# USB_Hub_AMCbox.net
KiCad netlist of a schematic drawn in Altium Designer
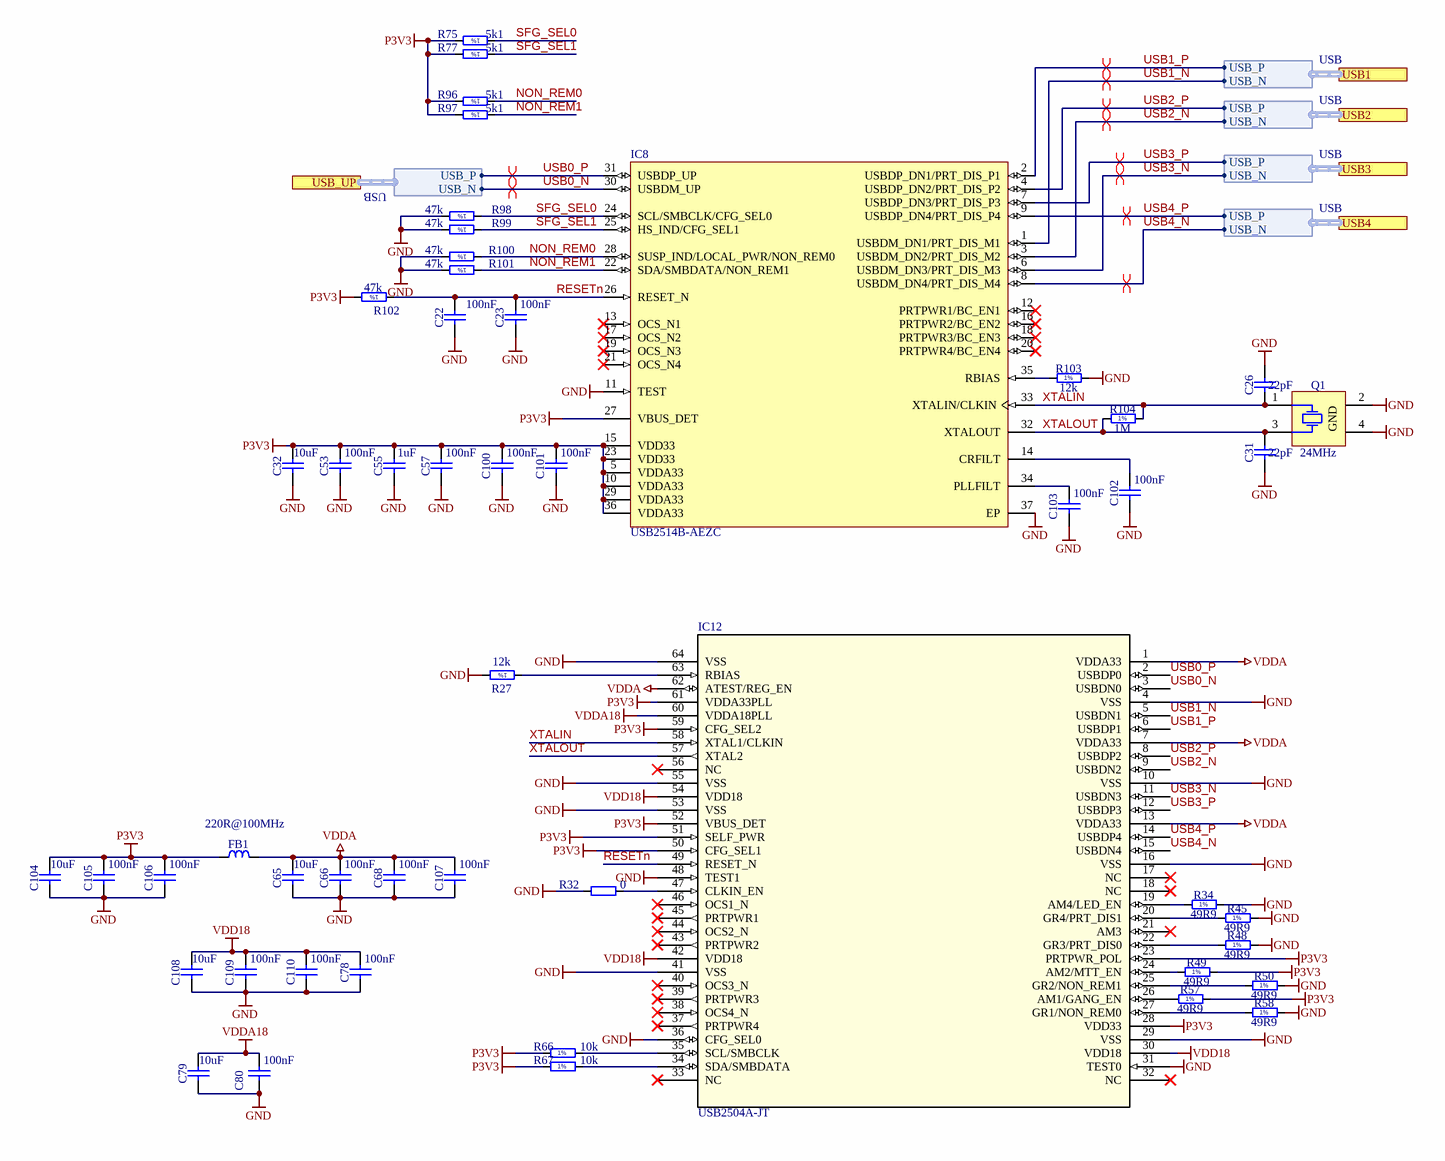
[diagram p0: USB_Hub_AMCbox.SchDoc]

(export (version "E")
  (design (tool "Eeschema 10.0.6"))
  (components
    (comp (ref "C22")
      (value "100nF")
      (footprint "CAPC0603X33N")
      (description "Non-polarised capacitor")
      (fields
        (field (name "PART NUMBER") "CC0201_100NF_6.3V_10%_X5R")
        (field (name "VOLTAGE") "6.3V")
        (field (name "AUTHOR") "CERN DEM JLC")
      )
      (libsource (lib "Capacitors") (part "Capacitor - non polarized"))
    )
    (comp (ref "C23")
      (value "100nF")
      (footprint "CAPC0603X33N")
      (description "Non-polarised capacitor")
      (fields
        (field (name "PART NUMBER") "CC0201_100NF_6.3V_10%_X5R")
        (field (name "VOLTAGE") "6.3V")
        (field (name "AUTHOR") "CERN DEM JLC")
      )
      (libsource (lib "Capacitors") (part "Capacitor - non polarized"))
    )
    (comp (ref "C26")
      (value "22pF")
      (footprint "CAPC1005X55N")
      (description "Non-polarised capacitor")
      (fields
        (field (name "PART NUMBER") "CC0402_22PF_50V_5%_C0G")
        (field (name "VOLTAGE") "50V")
        (field (name "AUTHOR") "CERN DEM JLC")
      )
      (libsource (lib "Capacitors") (part "Capacitor - non polarized"))
    )
    (comp (ref "C31")
      (value "22pF")
      (footprint "CAPC1005X55N")
      (description "Non-polarised capacitor")
      (fields
        (field (name "PART NUMBER") "CC0402_22PF_50V_5%_C0G")
        (field (name "VOLTAGE") "50V")
        (field (name "AUTHOR") "CERN DEM JLC")
      )
      (libsource (lib "Capacitors") (part "Capacitor - non polarized"))
    )
    (comp (ref "C32")
      (value "10uF")
      (footprint "CAPC1608X80N")
      (description "Non-polarised capacitor")
      (fields
        (field (name "PART NUMBER") "CC0603_10UF_16V_20%_X5R")
        (field (name "VOLTAGE") "16V")
        (field (name "AUTHOR") "CERN DEM MR")
      )
      (libsource (lib "Capacitors") (part "Capacitor - non polarized"))
    )
    (comp (ref "C53")
      (value "100nF")
      (footprint "CAPC0603X33N")
      (description "Non-polarised capacitor")
      (fields
        (field (name "PART NUMBER") "CC0201_100NF_6.3V_10%_X5R")
        (field (name "VOLTAGE") "6.3V")
        (field (name "AUTHOR") "CERN DEM JLC")
      )
      (libsource (lib "Capacitors") (part "Capacitor - non polarized"))
    )
    (comp (ref "C55")
      (value "1uF")
      (footprint "CAPC1005X55N")
      (description "Non-polarised capacitor")
      (fields
        (field (name "PART NUMBER") "CC0402_1UF_16V_10%_X5R")
        (field (name "VOLTAGE") "16V")
        (field (name "AUTHOR") "CERN DEM JLC")
      )
      (libsource (lib "Capacitors") (part "Capacitor - non polarized"))
    )
    (comp (ref "C57")
      (value "100nF")
      (footprint "CAPC0603X33N")
      (description "Non-polarised capacitor")
      (fields
        (field (name "PART NUMBER") "CC0201_100NF_6.3V_10%_X5R")
        (field (name "VOLTAGE") "6.3V")
        (field (name "AUTHOR") "CERN DEM JLC")
      )
      (libsource (lib "Capacitors") (part "Capacitor - non polarized"))
    )
    (comp (ref "C65")
      (value "10uF")
      (footprint "CAPC1608X80N")
      (description "Non-polarised capacitor")
      (fields
        (field (name "PART NUMBER") "CC0603_10UF_16V_20%_X5R")
        (field (name "VOLTAGE") "16V")
        (field (name "AUTHOR") "CERN DEM MR")
      )
      (libsource (lib "Capacitors") (part "Capacitor - non polarized"))
    )
    (comp (ref "C66")
      (value "100nF")
      (footprint "CAPC0603X33N")
      (description "Non-polarised capacitor")
      (fields
        (field (name "PART NUMBER") "CC0201_100NF_6.3V_10%_X5R")
        (field (name "VOLTAGE") "6.3V")
        (field (name "AUTHOR") "CERN DEM JLC")
      )
      (libsource (lib "Capacitors") (part "Capacitor - non polarized"))
    )
    (comp (ref "C68")
      (value "100nF")
      (footprint "CAPC0603X33N")
      (description "Non-polarised capacitor")
      (fields
        (field (name "PART NUMBER") "CC0201_100NF_6.3V_10%_X5R")
        (field (name "VOLTAGE") "6.3V")
        (field (name "AUTHOR") "CERN DEM JLC")
      )
      (libsource (lib "Capacitors") (part "Capacitor - non polarized"))
    )
    (comp (ref "C78")
      (value "100nF")
      (footprint "CAPC0603X33N")
      (description "Non-polarised capacitor")
      (fields
        (field (name "PART NUMBER") "CC0201_100NF_6.3V_10%_X5R")
        (field (name "VOLTAGE") "6.3V")
        (field (name "AUTHOR") "CERN DEM JLC")
      )
      (libsource (lib "Capacitors") (part "Capacitor - non polarized"))
    )
    (comp (ref "C79")
      (value "10uF")
      (footprint "CAPC1608X80N")
      (description "Non-polarised capacitor")
      (fields
        (field (name "PART NUMBER") "CC0603_10UF_16V_20%_X5R")
        (field (name "VOLTAGE") "16V")
        (field (name "AUTHOR") "CERN DEM MR")
      )
      (libsource (lib "Capacitors") (part "Capacitor - non polarized"))
    )
    (comp (ref "C80")
      (value "100nF")
      (footprint "CAPC0603X33N")
      (description "Non-polarised capacitor")
      (fields
        (field (name "PART NUMBER") "CC0201_100NF_6.3V_10%_X5R")
        (field (name "VOLTAGE") "6.3V")
        (field (name "AUTHOR") "CERN DEM JLC")
      )
      (libsource (lib "Capacitors") (part "Capacitor - non polarized"))
    )
    (comp (ref "C100")
      (value "100nF")
      (footprint "CAPC0603X33N")
      (description "Non-polarised capacitor")
      (fields
        (field (name "PART NUMBER") "CC0201_100NF_6.3V_10%_X5R")
        (field (name "VOLTAGE") "6.3V")
        (field (name "AUTHOR") "CERN DEM JLC")
      )
      (libsource (lib "Capacitors") (part "Capacitor - non polarized"))
    )
    (comp (ref "C101")
      (value "100nF")
      (footprint "CAPC0603X33N")
      (description "Non-polarised capacitor")
      (fields
        (field (name "PART NUMBER") "CC0201_100NF_6.3V_10%_X5R")
        (field (name "VOLTAGE") "6.3V")
        (field (name "AUTHOR") "CERN DEM JLC")
      )
      (libsource (lib "Capacitors") (part "Capacitor - non polarized"))
    )
    (comp (ref "C102")
      (value "100nF")
      (footprint "CAPC0603X33N")
      (description "Non-polarised capacitor")
      (fields
        (field (name "PART NUMBER") "CC0201_100NF_6.3V_10%_X5R")
        (field (name "VOLTAGE") "6.3V")
        (field (name "AUTHOR") "CERN DEM JLC")
      )
      (libsource (lib "Capacitors") (part "Capacitor - non polarized"))
    )
    (comp (ref "C103")
      (value "100nF")
      (footprint "CAPC0603X33N")
      (description "Non-polarised capacitor")
      (fields
        (field (name "PART NUMBER") "CC0201_100NF_6.3V_10%_X5R")
        (field (name "VOLTAGE") "6.3V")
        (field (name "AUTHOR") "CERN DEM JLC")
      )
      (libsource (lib "Capacitors") (part "Capacitor - non polarized"))
    )
    (comp (ref "C104")
      (value "10uF")
      (footprint "CAPC1608X80N")
      (description "Non-polarised capacitor")
      (fields
        (field (name "PART NUMBER") "CC0603_10UF_16V_20%_X5R")
        (field (name "VOLTAGE") "16V")
        (field (name "AUTHOR") "CERN DEM MR")
      )
      (libsource (lib "Capacitors") (part "Capacitor - non polarized"))
    )
    (comp (ref "C105")
      (value "100nF")
      (footprint "CAPC0603X33N")
      (description "Non-polarised capacitor")
      (fields
        (field (name "PART NUMBER") "CC0201_100NF_6.3V_10%_X5R")
        (field (name "VOLTAGE") "6.3V")
        (field (name "AUTHOR") "CERN DEM JLC")
      )
      (libsource (lib "Capacitors") (part "Capacitor - non polarized"))
    )
    (comp (ref "C106")
      (value "100nF")
      (footprint "CAPC0603X33N")
      (description "Non-polarised capacitor")
      (fields
        (field (name "PART NUMBER") "CC0201_100NF_6.3V_10%_X5R")
        (field (name "VOLTAGE") "6.3V")
        (field (name "AUTHOR") "CERN DEM JLC")
      )
      (libsource (lib "Capacitors") (part "Capacitor - non polarized"))
    )
    (comp (ref "C107")
      (value "100nF")
      (footprint "CAPC0603X33N")
      (description "Non-polarised capacitor")
      (fields
        (field (name "PART NUMBER") "CC0201_100NF_6.3V_10%_X5R")
        (field (name "VOLTAGE") "6.3V")
        (field (name "AUTHOR") "CERN DEM JLC")
      )
      (libsource (lib "Capacitors") (part "Capacitor - non polarized"))
    )
    (comp (ref "C108")
      (value "10uF")
      (footprint "CAPC1608X80N")
      (description "Non-polarised capacitor")
      (fields
        (field (name "PART NUMBER") "CC0603_10UF_16V_20%_X5R")
        (field (name "VOLTAGE") "16V")
        (field (name "AUTHOR") "CERN DEM MR")
      )
      (libsource (lib "Capacitors") (part "Capacitor - non polarized"))
    )
    (comp (ref "C109")
      (value "100nF")
      (footprint "CAPC0603X33N")
      (description "Non-polarised capacitor")
      (fields
        (field (name "PART NUMBER") "CC0201_100NF_6.3V_10%_X5R")
        (field (name "VOLTAGE") "6.3V")
        (field (name "AUTHOR") "CERN DEM JLC")
      )
      (libsource (lib "Capacitors") (part "Capacitor - non polarized"))
    )
    (comp (ref "C110")
      (value "100nF")
      (footprint "CAPC0603X33N")
      (description "Non-polarised capacitor")
      (fields
        (field (name "PART NUMBER") "CC0201_100NF_6.3V_10%_X5R")
        (field (name "VOLTAGE") "6.3V")
        (field (name "AUTHOR") "CERN DEM JLC")
      )
      (libsource (lib "Capacitors") (part "Capacitor - non polarized"))
    )
    (comp (ref "FB1")
      (value "220R@100MHz")
      (footprint "INDC2012X105N")
      (description "Inductor")
      (fields
        (field (name "PART NUMBER") "IND0805_MURATA_BLM21PG221SN1D")
        (field (name "POWER") "2A")
        (field (name "AUTHOR") "CERN DEM JLC")
      )
      (libsource (lib "Inductors & Transformers") (part "Inductor"))
    )
    (comp (ref "IC8")
      (value "USB2514B-AEZC")
      (footprint "MCHP-QFN-36_V")
      (description "USB 2.0 High-Speed Hub Controller, 4 Ports, 3 to 3.6 V, 0 to 85 degC, 36-Pin QFN, RoHS, Tray")
      (fields (field (name "MANUFACTURER") "Microchip"))
      (libsource (lib "Altium Content Vault") (part "MCHP-USB2514B-QFN-36"))
    )
    (comp (ref "IC12")
      (value "USB2504A-JT")
      (footprint "TQFP64_10x10MC_MCH")
      (description "Integrated USB 2.0 Compatible 4-Port Hub")
      (fields
        (field (name "MANUFACTURER") "Microchip")
        (field (name "COPYRIGHT") "Copyright (C) 2022 Ultra Librarian. All rights reserved.")
      )
      (libsource (lib "ICs_Analog_Interfaces") (part "IFC_USB2504A-JT"))
    )
    (comp (ref "Q1")
      (value "24MHz")
      (footprint "XTAL_PERICOM_FL")
      (description "Crystal 4 pins 1=XTAL Control 2=GND3=XTAL 4=GND")
      (fields
        (field (name "PART NUMBER") "XTAL_24MHZ_PERICOM_FL2400041")
        (field (name "MANUFACTURER") "PERICOM")
        (field (name "AUTHOR") "CERN DEM JLC")
      )
      (libsource (lib "ICs And Semiconductors") (part "Quartz Crystal 1X 2GND 3X 4GND"))
    )
    (comp (ref "R27")
      (value "12k")
      (footprint "RESC1005X40N")
      (description "Resistor - 1%")
      (fields
        (field (name "PART NUMBER") "R0402_12K_1%_0.0625W_100PPM")
        (field (name "POWER") "0.0625W")
        (field (name "AUTHOR") "CERN DEM JLC")
      )
      (libsource (lib "Resistors") (part "Resistor - 1%"))
    )
    (comp (ref "R32")
      (value "0")
      (footprint "RESC1005X40N")
      (description "Resistor")
      (fields
        (field (name "PART NUMBER") "R0402_0R_JUMPER")
        (field (name "MANUFACTURER") "GENERIC")
        (field (name "AUTHOR") "CERN DEM JLC")
      )
      (libsource (lib "Resistors") (part "Resistor"))
    )
    (comp (ref "R34")
      (value "49R9")
      (footprint "RESC1005X40N")
      (description "Resistor - 1%")
      (fields
        (field (name "PART NUMBER") "R0402_49R9_1%_0.0625W_100PPM")
        (field (name "POWER") "0.0625W")
        (field (name "AUTHOR") "CERN DEM JLC")
      )
      (libsource (lib "Resistors") (part "Resistor - 1%"))
    )
    (comp (ref "R45")
      (value "49R9")
      (footprint "RESC1005X40N")
      (description "Resistor - 1%")
      (fields
        (field (name "PART NUMBER") "R0402_49R9_1%_0.0625W_100PPM")
        (field (name "POWER") "0.0625W")
        (field (name "AUTHOR") "CERN DEM JLC")
      )
      (libsource (lib "Resistors") (part "Resistor - 1%"))
    )
    (comp (ref "R48")
      (value "49R9")
      (footprint "RESC1005X40N")
      (description "Resistor - 1%")
      (fields
        (field (name "PART NUMBER") "R0402_49R9_1%_0.0625W_100PPM")
        (field (name "POWER") "0.0625W")
        (field (name "AUTHOR") "CERN DEM JLC")
      )
      (libsource (lib "Resistors") (part "Resistor - 1%"))
    )
    (comp (ref "R49")
      (value "49R9")
      (footprint "RESC1005X40N")
      (description "Resistor - 1%")
      (fields
        (field (name "PART NUMBER") "R0402_49R9_1%_0.0625W_100PPM")
        (field (name "POWER") "0.0625W")
        (field (name "AUTHOR") "CERN DEM JLC")
      )
      (libsource (lib "Resistors") (part "Resistor - 1%"))
    )
    (comp (ref "R50")
      (value "49R9")
      (footprint "RESC1005X40N")
      (description "Resistor - 1%")
      (fields
        (field (name "PART NUMBER") "R0402_49R9_1%_0.0625W_100PPM")
        (field (name "POWER") "0.0625W")
        (field (name "AUTHOR") "CERN DEM JLC")
      )
      (libsource (lib "Resistors") (part "Resistor - 1%"))
    )
    (comp (ref "R57")
      (value "49R9")
      (footprint "RESC1005X40N")
      (description "Resistor - 1%")
      (fields
        (field (name "PART NUMBER") "R0402_49R9_1%_0.0625W_100PPM")
        (field (name "POWER") "0.0625W")
        (field (name "AUTHOR") "CERN DEM JLC")
      )
      (libsource (lib "Resistors") (part "Resistor - 1%"))
    )
    (comp (ref "R58")
      (value "49R9")
      (footprint "RESC1005X40N")
      (description "Resistor - 1%")
      (fields
        (field (name "PART NUMBER") "R0402_49R9_1%_0.0625W_100PPM")
        (field (name "POWER") "0.0625W")
        (field (name "AUTHOR") "CERN DEM JLC")
      )
      (libsource (lib "Resistors") (part "Resistor - 1%"))
    )
    (comp (ref "R66")
      (value "10k")
      (footprint "RESC1005X40N")
      (description "Resistor - 1%")
      (fields
        (field (name "PART NUMBER") "R0402_10K_1%_0.0625W_100PPM")
        (field (name "POWER") "0.0625W")
        (field (name "AUTHOR") "CERN DEM JLC")
      )
      (libsource (lib "Resistors") (part "Resistor - 1%"))
    )
    (comp (ref "R67")
      (value "10k")
      (footprint "RESC1005X40N")
      (description "Resistor - 1%")
      (fields
        (field (name "PART NUMBER") "R0402_10K_1%_0.0625W_100PPM")
        (field (name "POWER") "0.0625W")
        (field (name "AUTHOR") "CERN DEM JLC")
      )
      (libsource (lib "Resistors") (part "Resistor - 1%"))
    )
    (comp (ref "R75")
      (value "5k1")
      (footprint "RESC1005X40N")
      (description "Resistor - 1%")
      (fields
        (field (name "PART NUMBER") "R0402_5K1_1%_0.0625W_100PPM")
        (field (name "POWER") "0.0625W")
        (field (name "AUTHOR") "CERN DEM JLC")
      )
      (libsource (lib "Resistors") (part "Resistor - 1%"))
    )
    (comp (ref "R77")
      (value "5k1")
      (footprint "RESC1005X40N")
      (description "Resistor - 1%")
      (fields
        (field (name "PART NUMBER") "R0402_5K1_1%_0.0625W_100PPM")
        (field (name "POWER") "0.0625W")
        (field (name "AUTHOR") "CERN DEM JLC")
      )
      (libsource (lib "Resistors") (part "Resistor - 1%"))
    )
    (comp (ref "R96")
      (value "5k1")
      (footprint "RESC1005X40N")
      (description "Resistor - 1%")
      (fields
        (field (name "PART NUMBER") "R0402_5K1_1%_0.0625W_100PPM")
        (field (name "POWER") "0.0625W")
        (field (name "AUTHOR") "CERN DEM JLC")
      )
      (libsource (lib "Resistors") (part "Resistor - 1%"))
    )
    (comp (ref "R97")
      (value "5k1")
      (footprint "RESC1005X40N")
      (description "Resistor - 1%")
      (fields
        (field (name "PART NUMBER") "R0402_5K1_1%_0.0625W_100PPM")
        (field (name "POWER") "0.0625W")
        (field (name "AUTHOR") "CERN DEM JLC")
      )
      (libsource (lib "Resistors") (part "Resistor - 1%"))
    )
    (comp (ref "R98")
      (value "47k")
      (footprint "RESC1005X40N")
      (description "Resistor - 1%")
      (fields
        (field (name "MANUFACTURER PART NUMBER") "R0402_47K_1%_0.0625W_100PPM")
        (field (name "MANUFACTURER") "GENERIC")
        (field (name "AUTHOR") "CERN DEM JLC")
      )
      (libsource (lib "Resistors") (part "Resistor - 1%"))
    )
    (comp (ref "R99")
      (value "47k")
      (footprint "RESC1005X40N")
      (description "Resistor - 1%")
      (fields
        (field (name "MANUFACTURER PART NUMBER") "R0402_47K_1%_0.0625W_100PPM")
        (field (name "MANUFACTURER") "GENERIC")
        (field (name "AUTHOR") "CERN DEM JLC")
      )
      (libsource (lib "Resistors") (part "Resistor - 1%"))
    )
    (comp (ref "R100")
      (value "47k")
      (footprint "RESC1005X40N")
      (description "Resistor - 1%")
      (fields
        (field (name "MANUFACTURER PART NUMBER") "R0402_47K_1%_0.0625W_100PPM")
        (field (name "MANUFACTURER") "GENERIC")
        (field (name "AUTHOR") "CERN DEM JLC")
      )
      (libsource (lib "Resistors") (part "Resistor - 1%"))
    )
    (comp (ref "R101")
      (value "47k")
      (footprint "RESC1005X40N")
      (description "Resistor - 1%")
      (fields
        (field (name "MANUFACTURER PART NUMBER") "R0402_47K_1%_0.0625W_100PPM")
        (field (name "MANUFACTURER") "GENERIC")
        (field (name "AUTHOR") "CERN DEM JLC")
      )
      (libsource (lib "Resistors") (part "Resistor - 1%"))
    )
    (comp (ref "R102")
      (value "47k")
      (footprint "RESC1005X40N")
      (description "Resistor - 1%")
      (fields
        (field (name "MANUFACTURER PART NUMBER") "R0402_47K_1%_0.0625W_100PPM")
        (field (name "MANUFACTURER") "GENERIC")
        (field (name "AUTHOR") "CERN DEM JLC")
      )
      (libsource (lib "Resistors") (part "Resistor - 1%"))
    )
    (comp (ref "R103")
      (value "12k")
      (footprint "RESC1005X40N")
      (description "Resistor - 1%")
      (fields
        (field (name "PART NUMBER") "R0402_12K_1%_0.0625W_100PPM")
        (field (name "POWER") "0.0625W")
        (field (name "AUTHOR") "CERN DEM JLC")
      )
      (libsource (lib "Resistors") (part "Resistor - 1%"))
    )
    (comp (ref "R104")
      (value "1M")
      (footprint "RESC1005X40N")
      (description "Resistor - 1%")
      (fields
        (field (name "PART NUMBER") "R0402_1M_1%_0.0625W_100PPM")
        (field (name "POWER") "0.0625W")
        (field (name "AUTHOR") "CERN DEM JLC")
      )
      (libsource (lib "Resistors") (part "Resistor - 1%"))
    )
  )
  (nets
    (net (code "2") (name "/NON_REM0") (class "Default")
      (node (ref "IC8") (pin "28") (pinfunction "SUSP_IND/LOCAL_PWR/NON_REM0_28") (pintype "bidirectional"))
      (node (ref "R100") (pin "1") (pinfunction "1_1") (pintype "passive"))
      (node (ref "R96") (pin "1") (pinfunction "1_1") (pintype "passive"))
    )
    (net (code "3") (name "/NON_REM1") (class "Default")
      (node (ref "IC8") (pin "22") (pinfunction "SDA/SMBDATA/NON_REM1_22") (pintype "bidirectional"))
      (node (ref "R101") (pin "1") (pinfunction "1_1") (pintype "passive"))
      (node (ref "R97") (pin "1") (pinfunction "1_1") (pintype "passive"))
    )
    (net (code "4") (name "/RESETn") (class "Default")
      (node (ref "C22") (pin "2") (pinfunction "2_2") (pintype "passive"))
      (node (ref "C23") (pin "2") (pinfunction "2_2") (pintype "passive"))
      (node (ref "IC12") (pin "49") (pinfunction "RESET_N_49") (pintype "input"))
      (node (ref "IC8") (pin "26") (pinfunction "RESET_N_26") (pintype "input"))
      (node (ref "R102") (pin "1") (pinfunction "1_1") (pintype "passive"))
    )
    (net (code "5") (name "/SFG_SEL0") (class "Default")
      (node (ref "IC8") (pin "24") (pinfunction "SCL/SMBCLK/CFG_SEL0_24") (pintype "bidirectional"))
      (node (ref "R75") (pin "1") (pinfunction "1_1") (pintype "passive"))
      (node (ref "R98") (pin "1") (pinfunction "1_1") (pintype "passive"))
    )
    (net (code "6") (name "/SFG_SEL1") (class "Default")
      (node (ref "IC8") (pin "25") (pinfunction "HS_IND/CFG_SEL1_25") (pintype "bidirectional"))
      (node (ref "R77") (pin "1") (pinfunction "1_1") (pintype "passive"))
      (node (ref "R99") (pin "1") (pinfunction "1_1") (pintype "passive"))
    )
    (net (code "7") (name "/USB0_N") (class "Default")
      (node (ref "IC12") (pin "3") (pinfunction "USBDN0_3") (pintype "bidirectional"))
      (node (ref "IC8") (pin "30") (pinfunction "USBDM_UP_30") (pintype "bidirectional"))
    )
    (net (code "8") (name "/USB0_P") (class "Default")
      (node (ref "IC12") (pin "2") (pinfunction "USBDP0_2") (pintype "bidirectional"))
      (node (ref "IC8") (pin "31") (pinfunction "USBDP_UP_31") (pintype "bidirectional"))
    )
    (net (code "9") (name "/USB1_N") (class "Default")
      (node (ref "IC12") (pin "5") (pinfunction "USBDN1_5") (pintype "bidirectional"))
      (node (ref "IC8") (pin "1") (pinfunction "USBDM_DN1/PRT_DIS_M1_1") (pintype "bidirectional"))
    )
    (net (code "10") (name "/USB1_P") (class "Default")
      (node (ref "IC12") (pin "6") (pinfunction "USBDP1_6") (pintype "bidirectional"))
      (node (ref "IC8") (pin "2") (pinfunction "USBDP_DN1/PRT_DIS_P1_2") (pintype "bidirectional"))
    )
    (net (code "11") (name "/USB2_N") (class "Default")
      (node (ref "IC12") (pin "9") (pinfunction "USBDN2_9") (pintype "bidirectional"))
      (node (ref "IC8") (pin "3") (pinfunction "USBDM_DN2/PRT_DIS_M2_3") (pintype "bidirectional"))
    )
    (net (code "12") (name "/USB2_P") (class "Default")
      (node (ref "IC12") (pin "8") (pinfunction "USBDP2_8") (pintype "bidirectional"))
      (node (ref "IC8") (pin "4") (pinfunction "USBDP_DN2/PRT_DIS_P2_4") (pintype "bidirectional"))
    )
    (net (code "13") (name "/USB3_N") (class "Default")
      (node (ref "IC12") (pin "11") (pinfunction "USBDN3_11") (pintype "bidirectional"))
      (node (ref "IC8") (pin "6") (pinfunction "USBDM_DN3/PRT_DIS_M3_6") (pintype "bidirectional"))
    )
    (net (code "14") (name "/USB3_P") (class "Default")
      (node (ref "IC12") (pin "12") (pinfunction "USBDP3_12") (pintype "bidirectional"))
      (node (ref "IC8") (pin "7") (pinfunction "USBDP_DN3/PRT_DIS_P3_7") (pintype "bidirectional"))
    )
    (net (code "15") (name "/USB4_N") (class "Default")
      (node (ref "IC12") (pin "15") (pinfunction "USBDN4_15") (pintype "bidirectional"))
      (node (ref "IC8") (pin "8") (pinfunction "USBDM_DN4/PRT_DIS_M4_8") (pintype "bidirectional"))
    )
    (net (code "16") (name "/USB4_P") (class "Default")
      (node (ref "IC12") (pin "14") (pinfunction "USBDP4_14") (pintype "bidirectional"))
      (node (ref "IC8") (pin "9") (pinfunction "USBDP_DN4/PRT_DIS_P4_9") (pintype "bidirectional"))
    )
    (net (code "17") (name "/XTALIN") (class "Default")
      (node (ref "C26") (pin "1") (pinfunction "1_1") (pintype "passive"))
      (node (ref "IC12") (pin "58") (pinfunction "XTAL1/CLKIN_58") (pintype "input"))
      (node (ref "IC8") (pin "33") (pinfunction "XTALIN/CLKIN_33") (pintype "input"))
      (node (ref "Q1") (pin "1") (pinfunction "X_1") (pintype "passive"))
      (node (ref "R104") (pin "2") (pinfunction "2_2") (pintype "passive"))
    )
    (net (code "18") (name "/XTALOUT") (class "Default")
      (node (ref "C31") (pin "2") (pinfunction "2_2") (pintype "passive"))
      (node (ref "IC12") (pin "57") (pinfunction "XTAL2_57") (pintype "output"))
      (node (ref "IC8") (pin "32") (pinfunction "XTALOUT_32") (pintype "passive"))
      (node (ref "Q1") (pin "3") (pinfunction "X_3") (pintype "passive"))
      (node (ref "R104") (pin "1") (pinfunction "1_1") (pintype "passive"))
    )
    (net (code "20") (name "GND") (class "Default")
      (node (ref "C100") (pin "1") (pinfunction "1_1") (pintype "passive"))
      (node (ref "C101") (pin "1") (pinfunction "1_1") (pintype "passive"))
      (node (ref "C102") (pin "1") (pinfunction "1_1") (pintype "passive"))
      (node (ref "C103") (pin "1") (pinfunction "1_1") (pintype "passive"))
      (node (ref "C104") (pin "1") (pinfunction "1_1") (pintype "passive"))
      (node (ref "C105") (pin "1") (pinfunction "1_1") (pintype "passive"))
      (node (ref "C106") (pin "1") (pinfunction "1_1") (pintype "passive"))
      (node (ref "C107") (pin "1") (pinfunction "1_1") (pintype "passive"))
      (node (ref "C108") (pin "1") (pinfunction "1_1") (pintype "passive"))
      (node (ref "C109") (pin "1") (pinfunction "1_1") (pintype "passive"))
      (node (ref "C110") (pin "1") (pinfunction "1_1") (pintype "passive"))
      (node (ref "C22") (pin "1") (pinfunction "1_1") (pintype "passive"))
      (node (ref "C23") (pin "1") (pinfunction "1_1") (pintype "passive"))
      (node (ref "C26") (pin "2") (pinfunction "2_2") (pintype "passive"))
      (node (ref "C31") (pin "1") (pinfunction "1_1") (pintype "passive"))
      (node (ref "C32") (pin "1") (pinfunction "1_1") (pintype "passive"))
      (node (ref "C53") (pin "1") (pinfunction "1_1") (pintype "passive"))
      (node (ref "C55") (pin "1") (pinfunction "1_1") (pintype "passive"))
      (node (ref "C57") (pin "1") (pinfunction "1_1") (pintype "passive"))
      (node (ref "C65") (pin "1") (pinfunction "1_1") (pintype "passive"))
      (node (ref "C66") (pin "1") (pinfunction "1_1") (pintype "passive"))
      (node (ref "C68") (pin "1") (pinfunction "1_1") (pintype "passive"))
      (node (ref "C78") (pin "1") (pinfunction "1_1") (pintype "passive"))
      (node (ref "C79") (pin "1") (pinfunction "1_1") (pintype "passive"))
      (node (ref "C80") (pin "1") (pinfunction "1_1") (pintype "passive"))
      (node (ref "IC12") (pin "10") (pinfunction "VSS_10") (pintype "power_in"))
      (node (ref "IC12") (pin "16") (pinfunction "VSS_16") (pintype "power_in"))
      (node (ref "IC12") (pin "29") (pinfunction "VSS_29") (pintype "power_in"))
      (node (ref "IC12") (pin "31") (pinfunction "TEST0_31") (pintype "input"))
      (node (ref "IC12") (pin "36") (pinfunction "CFG_SEL0_36") (pintype "bidirectional"))
      (node (ref "IC12") (pin "4") (pinfunction "VSS_4") (pintype "power_in"))
      (node (ref "IC12") (pin "41") (pinfunction "VSS_41") (pintype "power_in"))
      (node (ref "IC12") (pin "48") (pinfunction "TEST1_48") (pintype "input"))
      (node (ref "IC12") (pin "53") (pinfunction "VSS_53") (pintype "power_in"))
      (node (ref "IC12") (pin "55") (pinfunction "VSS_55") (pintype "power_in"))
      (node (ref "IC12") (pin "64") (pinfunction "VSS_64") (pintype "power_in"))
      (node (ref "IC8") (pin "11") (pinfunction "TEST_11") (pintype "input"))
      (node (ref "IC8") (pin "37") (pinfunction "EP_37") (pintype "power_in"))
      (node (ref "Q1") (pin "2") (pinfunction "GND_2") (pintype "power_in"))
      (node (ref "Q1") (pin "4") (pinfunction "GND_4") (pintype "power_in"))
      (node (ref "R100") (pin "2") (pinfunction "2_2") (pintype "passive"))
      (node (ref "R101") (pin "2") (pinfunction "2_2") (pintype "passive"))
      (node (ref "R103") (pin "2") (pinfunction "2_2") (pintype "passive"))
      (node (ref "R27") (pin "2") (pinfunction "2_2") (pintype "passive"))
      (node (ref "R32") (pin "1") (pinfunction "1_1") (pintype "passive"))
      (node (ref "R34") (pin "2") (pinfunction "2_2") (pintype "passive"))
      (node (ref "R45") (pin "2") (pinfunction "2_2") (pintype "passive"))
      (node (ref "R48") (pin "2") (pinfunction "2_2") (pintype "passive"))
      (node (ref "R50") (pin "2") (pinfunction "2_2") (pintype "passive"))
      (node (ref "R58") (pin "2") (pinfunction "2_2") (pintype "passive"))
      (node (ref "R98") (pin "2") (pinfunction "2_2") (pintype "passive"))
      (node (ref "R99") (pin "2") (pinfunction "2_2") (pintype "passive"))
    )
    (net (code "21") (name "Net-(IC8-CRFILT)") (class "Default")
      (node (ref "C102") (pin "2") (pinfunction "2_2") (pintype "passive"))
      (node (ref "IC8") (pin "14") (pinfunction "CRFILT_14") (pintype "passive"))
    )
    (net (code "22") (name "Net-(IC8-PLLFILT)") (class "Default")
      (node (ref "C103") (pin "2") (pinfunction "2_2") (pintype "passive"))
      (node (ref "IC8") (pin "34") (pinfunction "PLLFILT_34") (pintype "passive"))
    )
    (net (code "23") (name "Net-(IC8-RBIAS)") (class "Default")
      (node (ref "IC8") (pin "35") (pinfunction "RBIAS_35") (pintype "input"))
      (node (ref "R103") (pin "1") (pinfunction "1_1") (pintype "passive"))
    )
    (net (code "24") (name "Net-(IC12-AM1{slash}GANG_EN)") (class "Default")
      (node (ref "IC12") (pin "26") (pinfunction "AM1/GANG_EN_26") (pintype "bidirectional"))
      (node (ref "R57") (pin "1") (pinfunction "1_1") (pintype "passive"))
    )
    (net (code "25") (name "Net-(IC12-AM2{slash}MTT_EN)") (class "Default")
      (node (ref "IC12") (pin "24") (pinfunction "AM2/MTT_EN_24") (pintype "bidirectional"))
      (node (ref "R49") (pin "1") (pinfunction "1_1") (pintype "passive"))
    )
    (net (code "26") (name "Net-(IC12-AM4{slash}LED_EN)") (class "Default")
      (node (ref "IC12") (pin "19") (pinfunction "AM4/LED_EN_19") (pintype "bidirectional"))
      (node (ref "R34") (pin "1") (pinfunction "1_1") (pintype "passive"))
    )
    (net (code "27") (name "Net-(IC12-CLKIN_EN)") (class "Default")
      (node (ref "IC12") (pin "47") (pinfunction "CLKIN_EN_47") (pintype "input"))
      (node (ref "R32") (pin "2") (pinfunction "2_2") (pintype "passive"))
    )
    (net (code "28") (name "Net-(IC12-GR1{slash}NON_REM0)") (class "Default")
      (node (ref "IC12") (pin "27") (pinfunction "GR1/NON_REM0_27") (pintype "bidirectional"))
      (node (ref "R58") (pin "1") (pinfunction "1_1") (pintype "passive"))
    )
    (net (code "29") (name "Net-(IC12-GR2{slash}NON_REM1)") (class "Default")
      (node (ref "IC12") (pin "25") (pinfunction "GR2/NON_REM1_25") (pintype "bidirectional"))
      (node (ref "R50") (pin "1") (pinfunction "1_1") (pintype "passive"))
    )
    (net (code "30") (name "Net-(IC12-GR3{slash}PRT_DIS0)") (class "Default")
      (node (ref "IC12") (pin "22") (pinfunction "GR3/PRT_DIS0_22") (pintype "bidirectional"))
      (node (ref "R48") (pin "1") (pinfunction "1_1") (pintype "passive"))
    )
    (net (code "31") (name "Net-(IC12-GR4{slash}PRT_DIS1)") (class "Default")
      (node (ref "IC12") (pin "20") (pinfunction "GR4/PRT_DIS1_20") (pintype "bidirectional"))
      (node (ref "R45") (pin "1") (pinfunction "1_1") (pintype "passive"))
    )
    (net (code "32") (name "Net-(IC12-RBIAS)") (class "Default")
      (node (ref "IC12") (pin "63") (pinfunction "RBIAS_63") (pintype "input"))
      (node (ref "R27") (pin "1") (pinfunction "1_1") (pintype "passive"))
    )
    (net (code "33") (name "Net-(IC12-SCL{slash}SMBCLK)") (class "Default")
      (node (ref "IC12") (pin "35") (pinfunction "SCL/SMBCLK_35") (pintype "bidirectional"))
      (node (ref "R66") (pin "2") (pinfunction "2_2") (pintype "passive"))
    )
    (net (code "34") (name "Net-(IC12-SDA{slash}SMBDATA)") (class "Default")
      (node (ref "IC12") (pin "34") (pinfunction "SDA/SMBDATA_34") (pintype "bidirectional"))
      (node (ref "R67") (pin "2") (pinfunction "2_2") (pintype "passive"))
    )
    (net (code "35") (name "P3V3") (class "Default")
      (node (ref "C100") (pin "2") (pinfunction "2_2") (pintype "passive"))
      (node (ref "C101") (pin "2") (pinfunction "2_2") (pintype "passive"))
      (node (ref "C104") (pin "2") (pinfunction "2_2") (pintype "passive"))
      (node (ref "C105") (pin "2") (pinfunction "2_2") (pintype "passive"))
      (node (ref "C106") (pin "2") (pinfunction "2_2") (pintype "passive"))
      (node (ref "C32") (pin "2") (pinfunction "2_2") (pintype "passive"))
      (node (ref "C53") (pin "2") (pinfunction "2_2") (pintype "passive"))
      (node (ref "C55") (pin "2") (pinfunction "2_2") (pintype "passive"))
      (node (ref "C57") (pin "2") (pinfunction "2_2") (pintype "passive"))
      (node (ref "FB1") (pin "1") (pinfunction "1_1") (pintype "passive"))
      (node (ref "IC12") (pin "23") (pinfunction "PRTPWR_POL_23") (pintype "bidirectional"))
      (node (ref "IC12") (pin "28") (pinfunction "VDD33_28") (pintype "power_in"))
      (node (ref "IC12") (pin "50") (pinfunction "CFG_SEL1_50") (pintype "input"))
      (node (ref "IC12") (pin "51") (pinfunction "SELF_PWR_51") (pintype "input"))
      (node (ref "IC12") (pin "52") (pinfunction "VBUS_DET_52") (pintype "power_in"))
      (node (ref "IC12") (pin "59") (pinfunction "CFG_SEL2_59") (pintype "input"))
      (node (ref "IC12") (pin "61") (pinfunction "VDDA33PLL_61") (pintype "power_in"))
      (node (ref "IC8") (pin "10") (pinfunction "VDDA33_10") (pintype "power_in"))
      (node (ref "IC8") (pin "15") (pinfunction "VDD33_15") (pintype "power_in"))
      (node (ref "IC8") (pin "23") (pinfunction "VDD33_23") (pintype "power_in"))
      (node (ref "IC8") (pin "27") (pinfunction "VBUS_DET_27") (pintype "power_in"))
      (node (ref "IC8") (pin "29") (pinfunction "VDDA33_29") (pintype "power_in"))
      (node (ref "IC8") (pin "36") (pinfunction "VDDA33_36") (pintype "power_in"))
      (node (ref "IC8") (pin "5") (pinfunction "VDDA33_5") (pintype "power_in"))
      (node (ref "R102") (pin "2") (pinfunction "2_2") (pintype "passive"))
      (node (ref "R49") (pin "2") (pinfunction "2_2") (pintype "passive"))
      (node (ref "R57") (pin "2") (pinfunction "2_2") (pintype "passive"))
      (node (ref "R66") (pin "1") (pinfunction "1_1") (pintype "passive"))
      (node (ref "R67") (pin "1") (pinfunction "1_1") (pintype "passive"))
      (node (ref "R75") (pin "2") (pinfunction "2_2") (pintype "passive"))
      (node (ref "R77") (pin "2") (pinfunction "2_2") (pintype "passive"))
      (node (ref "R96") (pin "2") (pinfunction "2_2") (pintype "passive"))
      (node (ref "R97") (pin "2") (pinfunction "2_2") (pintype "passive"))
    )
    (net (code "36") (name "VDD18") (class "Default")
      (node (ref "C108") (pin "2") (pinfunction "2_2") (pintype "passive"))
      (node (ref "C109") (pin "2") (pinfunction "2_2") (pintype "passive"))
      (node (ref "C110") (pin "2") (pinfunction "2_2") (pintype "passive"))
      (node (ref "C78") (pin "2") (pinfunction "2_2") (pintype "passive"))
      (node (ref "IC12") (pin "30") (pinfunction "VDD18_30") (pintype "power_in"))
      (node (ref "IC12") (pin "42") (pinfunction "VDD18_42") (pintype "power_in"))
      (node (ref "IC12") (pin "54") (pinfunction "VDD18_54") (pintype "power_in"))
    )
    (net (code "37") (name "VDDA") (class "Default")
      (node (ref "C107") (pin "2") (pinfunction "2_2") (pintype "passive"))
      (node (ref "C65") (pin "2") (pinfunction "2_2") (pintype "passive"))
      (node (ref "C66") (pin "2") (pinfunction "2_2") (pintype "passive"))
      (node (ref "C68") (pin "2") (pinfunction "2_2") (pintype "passive"))
      (node (ref "FB1") (pin "2") (pinfunction "2_2") (pintype "passive"))
      (node (ref "IC12") (pin "1") (pinfunction "VDDA33_1") (pintype "power_in"))
      (node (ref "IC12") (pin "13") (pinfunction "VDDA33_13") (pintype "power_in"))
      (node (ref "IC12") (pin "62") (pinfunction "ATEST/REG_EN_62") (pintype "bidirectional"))
      (node (ref "IC12") (pin "7") (pinfunction "VDDA33_7") (pintype "power_in"))
    )
    (net (code "38") (name "VDDA18") (class "Default")
      (node (ref "C79") (pin "2") (pinfunction "2_2") (pintype "passive"))
      (node (ref "C80") (pin "2") (pinfunction "2_2") (pintype "passive"))
      (node (ref "IC12") (pin "60") (pinfunction "VDDA18PLL_60") (pintype "power_in"))
    )
    (net (code "39") (name "unconnected-(IC8-OCS_N1-Pad13)") (class "Default")
      (node (ref "IC8") (pin "13") (pinfunction "OCS_N1_13") (pintype "input+no_connect"))
    )
    (net (code "40") (name "unconnected-(IC8-OCS_N2-Pad17)") (class "Default")
      (node (ref "IC8") (pin "17") (pinfunction "OCS_N2_17") (pintype "input+no_connect"))
    )
    (net (code "41") (name "unconnected-(IC8-OCS_N3-Pad19)") (class "Default")
      (node (ref "IC8") (pin "19") (pinfunction "OCS_N3_19") (pintype "input+no_connect"))
    )
    (net (code "42") (name "unconnected-(IC8-OCS_N4-Pad21)") (class "Default")
      (node (ref "IC8") (pin "21") (pinfunction "OCS_N4_21") (pintype "input+no_connect"))
    )
    (net (code "43") (name "unconnected-(IC8-PRTPWR1{slash}BC_EN1-Pad12)") (class "Default")
      (node (ref "IC8") (pin "12") (pinfunction "PRTPWR1/BC_EN1_12") (pintype "bidirectional+no_connect"))
    )
    (net (code "44") (name "unconnected-(IC8-PRTPWR2{slash}BC_EN2-Pad16)") (class "Default")
      (node (ref "IC8") (pin "16") (pinfunction "PRTPWR2/BC_EN2_16") (pintype "bidirectional+no_connect"))
    )
    (net (code "45") (name "unconnected-(IC8-PRTPWR3{slash}BC_EN3-Pad18)") (class "Default")
      (node (ref "IC8") (pin "18") (pinfunction "PRTPWR3/BC_EN3_18") (pintype "bidirectional+no_connect"))
    )
    (net (code "46") (name "unconnected-(IC8-PRTPWR4{slash}BC_EN4-Pad20)") (class "Default")
      (node (ref "IC8") (pin "20") (pinfunction "PRTPWR4/BC_EN4_20") (pintype "bidirectional+no_connect"))
    )
    (net (code "47") (name "unconnected-(IC12-AM3-Pad21)") (class "Default")
      (node (ref "IC12") (pin "21") (pinfunction "AM3_21") (pintype "bidirectional+no_connect"))
    )
    (net (code "48") (name "unconnected-(IC12-NC-Pad17)") (class "Default")
      (node (ref "IC12") (pin "17") (pinfunction "NC_17") (pintype "passive+no_connect"))
    )
    (net (code "49") (name "unconnected-(IC12-NC-Pad18)") (class "Default")
      (node (ref "IC12") (pin "18") (pinfunction "NC_18") (pintype "passive+no_connect"))
    )
    (net (code "50") (name "unconnected-(IC12-NC-Pad32)") (class "Default")
      (node (ref "IC12") (pin "32") (pinfunction "NC_32") (pintype "passive+no_connect"))
    )
    (net (code "51") (name "unconnected-(IC12-NC-Pad33)") (class "Default")
      (node (ref "IC12") (pin "33") (pinfunction "NC_33") (pintype "passive+no_connect"))
    )
    (net (code "52") (name "unconnected-(IC12-NC-Pad56)") (class "Default")
      (node (ref "IC12") (pin "56") (pinfunction "NC_56") (pintype "passive+no_connect"))
    )
    (net (code "53") (name "unconnected-(IC12-OCS1_N-Pad46)") (class "Default")
      (node (ref "IC12") (pin "46") (pinfunction "OCS1_N_46") (pintype "input+no_connect"))
    )
    (net (code "54") (name "unconnected-(IC12-OCS2_N-Pad44)") (class "Default")
      (node (ref "IC12") (pin "44") (pinfunction "OCS2_N_44") (pintype "input+no_connect"))
    )
    (net (code "55") (name "unconnected-(IC12-OCS3_N-Pad40)") (class "Default")
      (node (ref "IC12") (pin "40") (pinfunction "OCS3_N_40") (pintype "input+no_connect"))
    )
    (net (code "56") (name "unconnected-(IC12-OCS4_N-Pad38)") (class "Default")
      (node (ref "IC12") (pin "38") (pinfunction "OCS4_N_38") (pintype "input+no_connect"))
    )
    (net (code "57") (name "unconnected-(IC12-PRTPWR1-Pad45)") (class "Default")
      (node (ref "IC12") (pin "45") (pinfunction "PRTPWR1_45") (pintype "output+no_connect"))
    )
    (net (code "58") (name "unconnected-(IC12-PRTPWR2-Pad43)") (class "Default")
      (node (ref "IC12") (pin "43") (pinfunction "PRTPWR2_43") (pintype "output+no_connect"))
    )
    (net (code "59") (name "unconnected-(IC12-PRTPWR3-Pad39)") (class "Default")
      (node (ref "IC12") (pin "39") (pinfunction "PRTPWR3_39") (pintype "output+no_connect"))
    )
    (net (code "60") (name "unconnected-(IC12-PRTPWR4-Pad37)") (class "Default")
      (node (ref "IC12") (pin "37") (pinfunction "PRTPWR4_37") (pintype "output+no_connect"))
    )
  )
)
